# 556.net
KiCad netlist of a schematic drawn in EAGLE
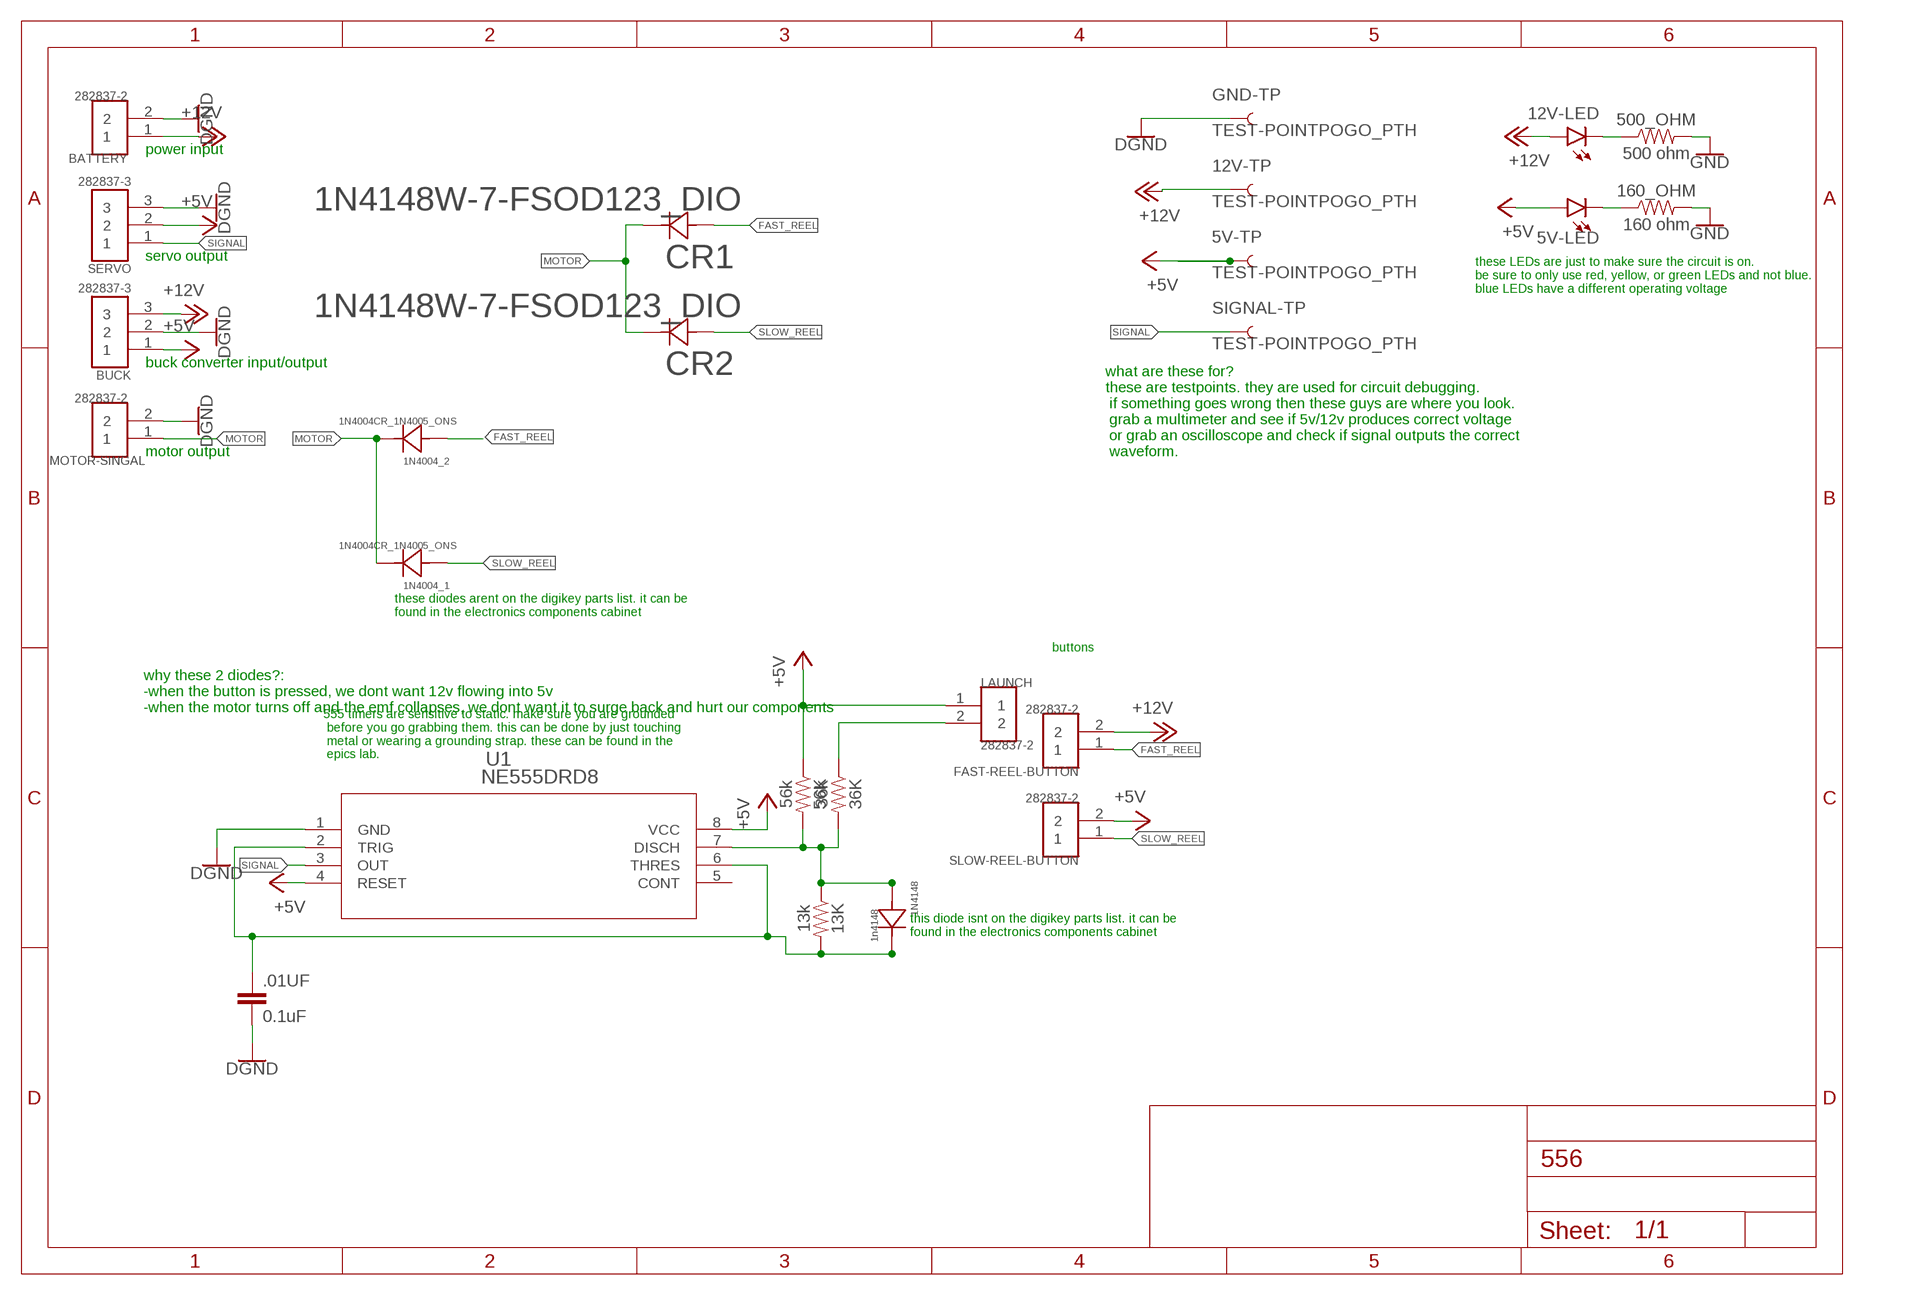
[diagram p0: schematic, sheet 1]

(export (version "E")
  (design (tool "Eeschema 10.0.6"))
  (components
    (comp (ref ".01UF")
      (value "0.1uF")
      (footprint "eagle-import:0402-CAP")
      (libsource (lib "eagle-import") (part ".1UF-CER"))
    )
    (comp (ref "1N4004_1")
      (value "1N4004CR_1N4005_ONS")
      (footprint "eagle-import:CR_1N4005_ONS")
      (fields
        (field (name "MANUFACTURER_PART_NUMBER") "1N4004")
        (field (name "COPYRIGHT") "Copyright (C) 2023 Ultra Librarian. All rights reserved.")
      )
      (libsource (lib "eagle-import") (part "1N4004CR_1N4005_ONS"))
    )
    (comp (ref "1N4004_2")
      (value "1N4004CR_1N4005_ONS")
      (footprint "eagle-import:CR_1N4005_ONS")
      (fields
        (field (name "MANUFACTURER_PART_NUMBER") "1N4004")
        (field (name "COPYRIGHT") "Copyright (C) 2023 Ultra Librarian. All rights reserved.")
      )
      (libsource (lib "eagle-import") (part "1N4004CR_1N4005_ONS"))
    )
    (comp (ref "1N4148")
      (value "1n4148")
      (footprint "eagle-import:CR_1N4005_ONS")
      (fields
        (field (name "MANUFACTURER_PART_NUMBER") "1N4004")
        (field (name "COPYRIGHT") "Copyright (C) 2023 Ultra Librarian. All rights reserved.")
      )
      (libsource (lib "eagle-import") (part "1N4004CR_1N4005_ONS"))
    )
    (comp (ref "5V-LED")
      (value "LED0603")
      (footprint "eagle-import:LED-0603")
      (libsource (lib "eagle-import") (part "LED0603"))
    )
    (comp (ref "5V-TP")
      (value "TEST-POINTPOGO_PTH")
      (footprint "eagle-import:1X01_NO_SILK")
      (libsource (lib "eagle-import") (part "TEST-POINTPOGO_PTH"))
    )
    (comp (ref "12V-LED")
      (value "LED0603")
      (footprint "eagle-import:LED-0603")
      (libsource (lib "eagle-import") (part "LED0603"))
    )
    (comp (ref "12V-TP")
      (value "TEST-POINTPOGO_PTH")
      (footprint "eagle-import:1X01_NO_SILK")
      (libsource (lib "eagle-import") (part "TEST-POINTPOGO_PTH"))
    )
    (comp (ref "13K")
      (value "13k")
      (footprint "eagle-import:0603")
      (libsource (lib "eagle-import") (part "1.8MOHM"))
    )
    (comp (ref "36K")
      (value "36k")
      (footprint "eagle-import:0603")
      (libsource (lib "eagle-import") (part "1.8MOHM"))
    )
    (comp (ref "56K")
      (value "56k")
      (footprint "eagle-import:0603")
      (libsource (lib "eagle-import") (part "1.8MOHM"))
    )
    (comp (ref "160_OHM")
      (value "160 ohm")
      (footprint "eagle-import:0603")
      (libsource (lib "eagle-import") (part "1.8MOHM"))
    )
    (comp (ref "500_OHM")
      (value "500 ohm")
      (footprint "eagle-import:0603")
      (libsource (lib "eagle-import") (part "1.8MOHM"))
    )
    (comp (ref "BATTERY")
      (value "282837-2")
      (footprint "eagle-import:TE_282837-2")
      (fields (field (name "DIGIKEY_PART_NUMBER") "A113320-ND") (field (name "MF") "TE Connectivity"))
      (libsource (lib "eagle-import") (part "282837-2"))
    )
    (comp (ref "BUCK")
      (value "282837-3")
      (footprint "eagle-import:TE_282837-3")
      (fields (field (name "MANUFACTURER") "TE CONNECTIVITY"))
      (libsource (lib "eagle-import") (part "282837-3"))
    )
    (comp (ref "CR1")
      (value "1N4148W-7-FSOD123_DIO")
      (footprint "eagle-import:SOD123_DIO")
      (fields
        (field (name "MANUFACTURER_PART_NUMBER") "1N4148W-7-F")
        (field (name "COPYRIGHT") "Copyright (C) 2023 Ultra Librarian. All rights reserved.")
      )
      (libsource (lib "eagle-import") (part "1N4148W-7-FSOD123_DIO"))
    )
    (comp (ref "CR2")
      (value "1N4148W-7-FSOD123_DIO")
      (footprint "eagle-import:SOD123_DIO")
      (fields
        (field (name "MANUFACTURER_PART_NUMBER") "1N4148W-7-F")
        (field (name "COPYRIGHT") "Copyright (C) 2023 Ultra Librarian. All rights reserved.")
      )
      (libsource (lib "eagle-import") (part "1N4148W-7-FSOD123_DIO"))
    )
    (comp (ref "FAST-REEL-BUTTON")
      (value "282837-2")
      (footprint "eagle-import:TE_282837-2")
      (fields (field (name "DIGIKEY_PART_NUMBER") "A113320-ND") (field (name "MF") "TE Connectivity"))
      (libsource (lib "eagle-import") (part "282837-2"))
    )
    (comp (ref "GND-TP")
      (value "TEST-POINTPOGO_PTH")
      (footprint "eagle-import:1X01_NO_SILK")
      (libsource (lib "eagle-import") (part "TEST-POINTPOGO_PTH"))
    )
    (comp (ref "LAUNCH")
      (value "282837-2")
      (footprint "eagle-import:TE_282837-2")
      (fields (field (name "DIGIKEY_PART_NUMBER") "A113320-ND") (field (name "MF") "TE Connectivity"))
      (libsource (lib "eagle-import") (part "282837-2"))
    )
    (comp (ref "MOTOR-SINGAL")
      (value "282837-2")
      (footprint "eagle-import:TE_282837-2")
      (fields (field (name "DIGIKEY_PART_NUMBER") "A113320-ND") (field (name "MF") "TE Connectivity"))
      (libsource (lib "eagle-import") (part "282837-2"))
    )
    (comp (ref "SERVO")
      (value "282837-3")
      (footprint "eagle-import:TE_282837-3")
      (fields (field (name "MANUFACTURER") "TE CONNECTIVITY"))
      (libsource (lib "eagle-import") (part "282837-3"))
    )
    (comp (ref "SIGNAL-TP")
      (value "TEST-POINTPOGO_PTH")
      (footprint "eagle-import:1X01_NO_SILK")
      (libsource (lib "eagle-import") (part "TEST-POINTPOGO_PTH"))
    )
    (comp (ref "SLOW-REEL-BUTTON")
      (value "282837-2")
      (footprint "eagle-import:TE_282837-2")
      (fields (field (name "DIGIKEY_PART_NUMBER") "A113320-ND") (field (name "MF") "TE Connectivity"))
      (libsource (lib "eagle-import") (part "282837-2"))
    )
    (comp (ref "U1")
      (value "NE555DRD8")
      (footprint "eagle-import:D8")
      (fields
        (field (name "MANUFACTURER_PART_NUMBER") "NE555DR")
        (field (name "COPYRIGHT") "Copyright (C) 2023 Ultra Librarian. All rights reserved.")
      )
      (libsource (lib "eagle-import") (part "NE555DRD8"))
    )
  )
  (nets
    (net (code "1") (name "+5V") (class "Default")
      (node (ref "56K") (pin "1") (pinfunction "1_1") (pintype "passive"))
      (node (ref "5V-LED") (pin "A") (pinfunction "A_A") (pintype "passive"))
      (node (ref "5V-TP") (pin "1") (pinfunction "1_1") (pintype "bidirectional"))
      (node (ref "BUCK") (pin "1") (pinfunction "1_1") (pintype "passive"))
      (node (ref "LAUNCH") (pin "1") (pinfunction "1_1") (pintype "passive"))
      (node (ref "SERVO") (pin "2") (pinfunction "2_2") (pintype "passive"))
      (node (ref "SLOW-REEL-BUTTON") (pin "2") (pinfunction "2_2") (pintype "passive"))
      (node (ref "U1") (pin "4") (pinfunction "RESET_4") (pintype "input"))
      (node (ref "U1") (pin "8") (pinfunction "VCC_8") (pintype "power_in"))
    )
    (net (code "2") (name "+12V") (class "Default")
      (node (ref "12V-LED") (pin "A") (pinfunction "A_A") (pintype "passive"))
      (node (ref "12V-TP") (pin "1") (pinfunction "1_1") (pintype "bidirectional"))
      (node (ref "BATTERY") (pin "1") (pinfunction "1_1") (pintype "passive"))
      (node (ref "BUCK") (pin "3") (pinfunction "3_3") (pintype "passive"))
      (node (ref "FAST-REEL-BUTTON") (pin "2") (pinfunction "2_2") (pintype "passive"))
    )
    (net (code "3") (name "DGND") (class "Default")
      (node (ref ".01UF") (pin "2") (pinfunction "2_2") (pintype "passive"))
      (node (ref "160_OHM") (pin "2") (pinfunction "2_2") (pintype "passive"))
      (node (ref "500_OHM") (pin "2") (pinfunction "2_2") (pintype "passive"))
      (node (ref "BATTERY") (pin "2") (pinfunction "2_2") (pintype "passive"))
      (node (ref "BUCK") (pin "2") (pinfunction "2_2") (pintype "passive"))
      (node (ref "GND-TP") (pin "1") (pinfunction "1_1") (pintype "bidirectional"))
      (node (ref "MOTOR-SINGAL") (pin "2") (pinfunction "2_2") (pintype "passive"))
      (node (ref "SERVO") (pin "3") (pinfunction "3_3") (pintype "passive"))
      (node (ref "U1") (pin "1") (pinfunction "GND_1") (pintype "power_in"))
    )
    (net (code "4") (name "FAST_REEL") (class "Default")
      (node (ref "1N4004_2") (pin "2") (pinfunction "2_2") (pintype "passive"))
      (node (ref "CR1") (pin "2") (pinfunction "2_2") (pintype "passive"))
      (node (ref "FAST-REEL-BUTTON") (pin "1") (pinfunction "1_1") (pintype "passive"))
    )
    (net (code "5") (name "MOTOR") (class "Default")
      (node (ref "1N4004_1") (pin "1") (pinfunction "1_1") (pintype "passive"))
      (node (ref "1N4004_2") (pin "1") (pinfunction "1_1") (pintype "passive"))
      (node (ref "CR1") (pin "1") (pinfunction "1_1") (pintype "passive"))
      (node (ref "CR2") (pin "1") (pinfunction "1_1") (pintype "passive"))
      (node (ref "MOTOR-SINGAL") (pin "1") (pinfunction "1_1") (pintype "passive"))
    )
    (net (code "6") (name "Net-(12V-LED-PadC)") (class "Default")
      (node (ref "12V-LED") (pin "C") (pinfunction "C_C") (pintype "passive"))
      (node (ref "500_OHM") (pin "1") (pinfunction "1_1") (pintype "passive"))
    )
    (net (code "7") (name "Net-(36K-Pad1)") (class "Default")
      (node (ref "36K") (pin "1") (pinfunction "1_1") (pintype "passive"))
      (node (ref "LAUNCH") (pin "2") (pinfunction "2_2") (pintype "passive"))
    )
    (net (code "8") (name "Net-(160_OHM-Pad1)") (class "Default")
      (node (ref "160_OHM") (pin "1") (pinfunction "1_1") (pintype "passive"))
      (node (ref "5V-LED") (pin "C") (pinfunction "C_C") (pintype "passive"))
    )
    (net (code "9") (name "Net-(U1-DISCH)") (class "Default")
      (node (ref "13K") (pin "1") (pinfunction "1_1") (pintype "passive"))
      (node (ref "1N4148") (pin "2") (pinfunction "2_2") (pintype "passive"))
      (node (ref "36K") (pin "2") (pinfunction "2_2") (pintype "passive"))
      (node (ref "56K") (pin "2") (pinfunction "2_2") (pintype "passive"))
      (node (ref "U1") (pin "7") (pinfunction "DISCH_7") (pintype "passive"))
    )
    (net (code "10") (name "Net-(U1-THRES)") (class "Default")
      (node (ref ".01UF") (pin "1") (pinfunction "1_1") (pintype "passive"))
      (node (ref "13K") (pin "2") (pinfunction "2_2") (pintype "passive"))
      (node (ref "1N4148") (pin "1") (pinfunction "1_1") (pintype "passive"))
      (node (ref "U1") (pin "2") (pinfunction "TRIG_2") (pintype "input"))
      (node (ref "U1") (pin "6") (pinfunction "THRES_6") (pintype "input"))
    )
    (net (code "11") (name "SIGNAL") (class "Default")
      (node (ref "SERVO") (pin "1") (pinfunction "1_1") (pintype "passive"))
      (node (ref "SIGNAL-TP") (pin "1") (pinfunction "1_1") (pintype "bidirectional"))
      (node (ref "U1") (pin "3") (pinfunction "OUT_3") (pintype "output"))
    )
    (net (code "12") (name "SLOW_REEL") (class "Default")
      (node (ref "1N4004_1") (pin "2") (pinfunction "2_2") (pintype "passive"))
      (node (ref "CR2") (pin "2") (pinfunction "2_2") (pintype "passive"))
      (node (ref "SLOW-REEL-BUTTON") (pin "1") (pinfunction "1_1") (pintype "passive"))
    )
    (net (code "13") (name "unconnected-(U1-CONT-Pad5)") (class "Default")
      (node (ref "U1") (pin "5") (pinfunction "CONT_5") (pintype "passive"))
    )
  )
)
